# bn5_redraw.net
KiCad netlist of a schematic drawn in EAGLE
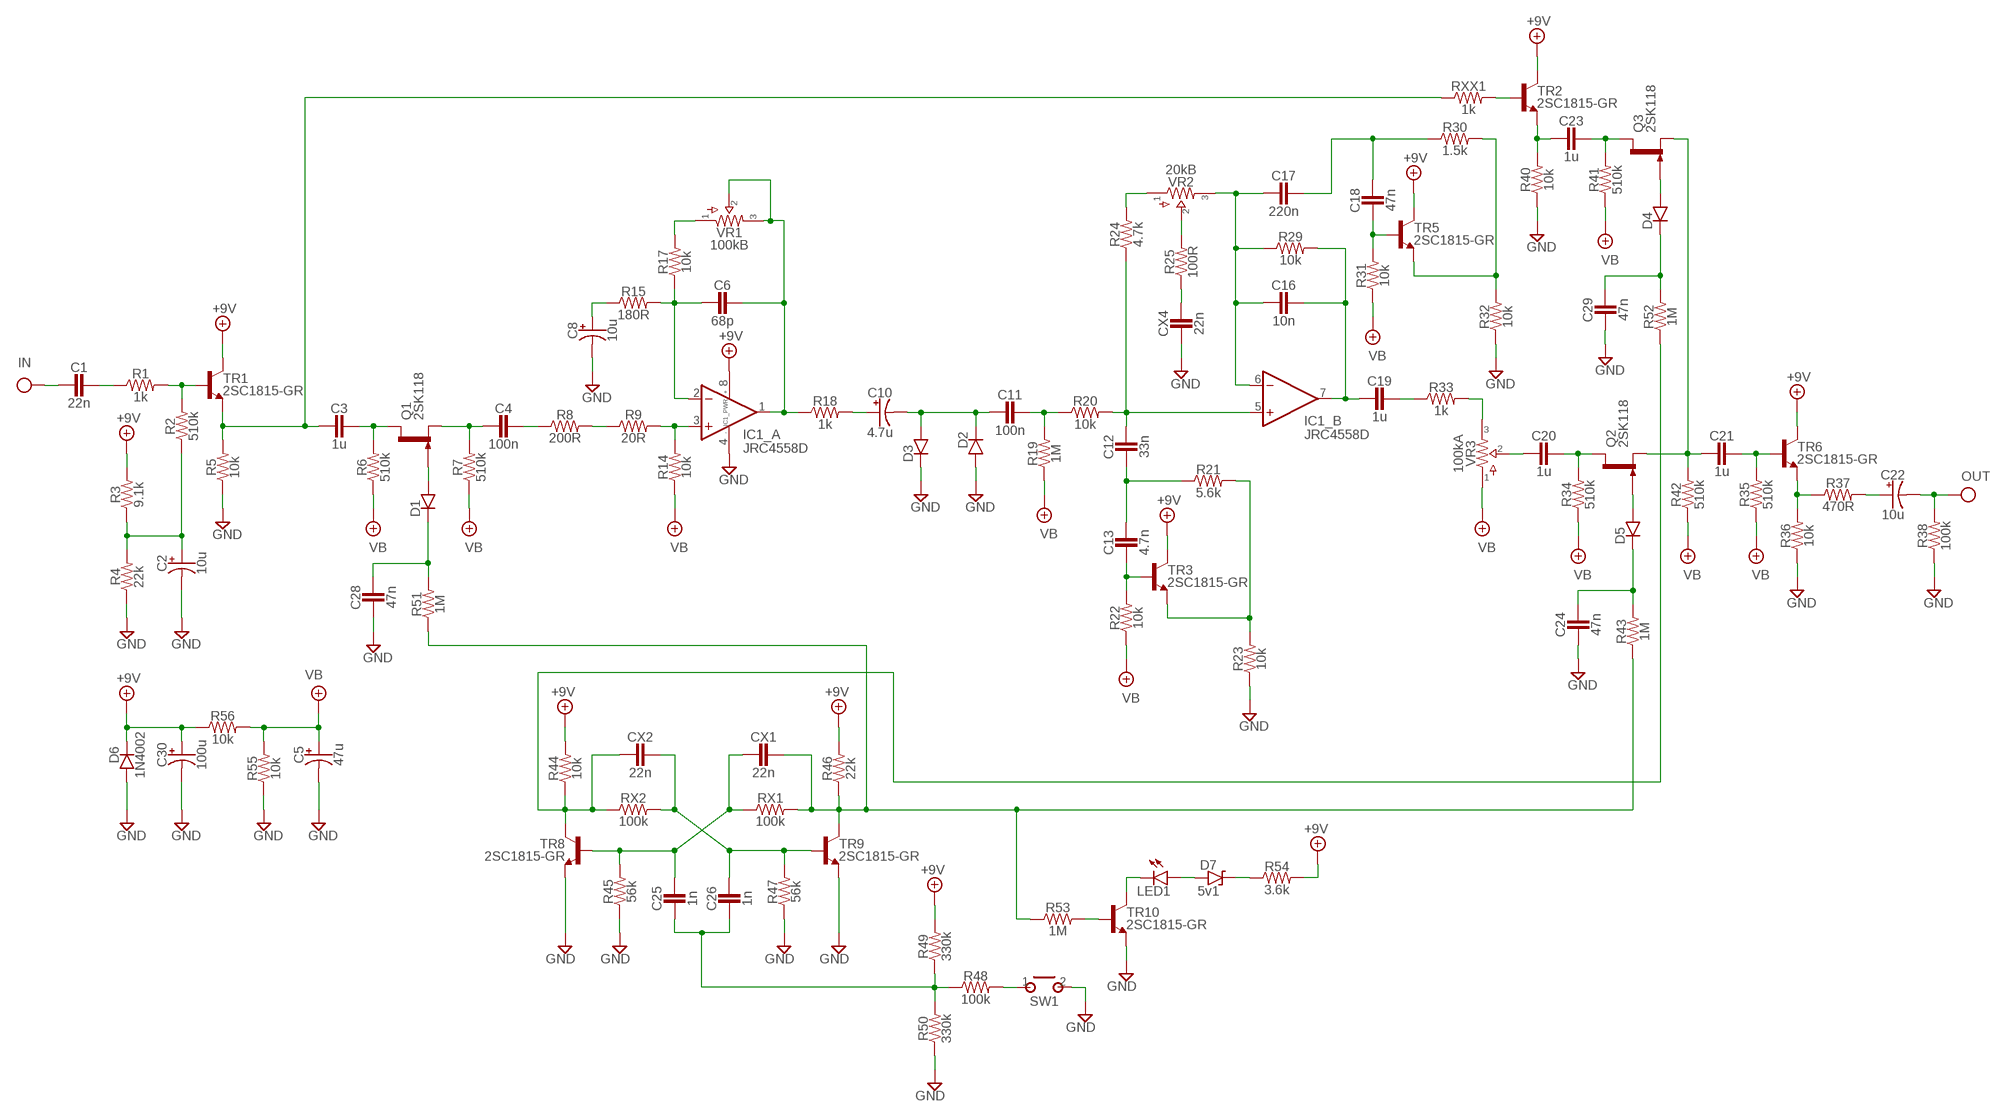
[diagram p0: schematic, sheet 1]

(export (version "E")
  (design (tool "Eeschema 10.0.6"))
  (components
    (comp (ref "C1")
      (value "22n")
      (footprint "eagle-import:BOX_SMALL")
      (libsource (lib "eagle-import") (part "CER/FILMBOX.1"))
    )
    (comp (ref "C2")
      (value "10u")
      (footprint "eagle-import:050_020")
      (libsource (lib "eagle-import") (part "0500"))
    )
    (comp (ref "C3")
      (value "1u")
      (footprint "eagle-import:BOX_SMALL")
      (libsource (lib "eagle-import") (part "CER/FILMBOX.1"))
    )
    (comp (ref "C4")
      (value "100n")
      (footprint "eagle-import:BOX_SMALL")
      (libsource (lib "eagle-import") (part "CER/FILMBOX.1"))
    )
    (comp (ref "C5")
      (value "47u")
      (footprint "eagle-import:050_020")
      (libsource (lib "eagle-import") (part "0500"))
    )
    (comp (ref "C6")
      (value "68p")
      (footprint "eagle-import:BOX_SMALL")
      (libsource (lib "eagle-import") (part "CER/FILMBOX.1"))
    )
    (comp (ref "C8")
      (value "10u")
      (footprint "eagle-import:050_020")
      (libsource (lib "eagle-import") (part "0500"))
    )
    (comp (ref "C10")
      (value "4.7u")
      (footprint "eagle-import:050_020")
      (libsource (lib "eagle-import") (part "0500"))
    )
    (comp (ref "C11")
      (value "100n")
      (footprint "eagle-import:BOX_SMALL")
      (libsource (lib "eagle-import") (part "CER/FILMBOX.1"))
    )
    (comp (ref "C12")
      (value "33n")
      (footprint "eagle-import:BOX_SMALL")
      (libsource (lib "eagle-import") (part "CER/FILMBOX.1"))
    )
    (comp (ref "C13")
      (value "4.7n")
      (footprint "eagle-import:BOX_SMALL")
      (libsource (lib "eagle-import") (part "CER/FILMBOX.1"))
    )
    (comp (ref "C16")
      (value "10n")
      (footprint "eagle-import:BOX_SMALL")
      (libsource (lib "eagle-import") (part "CER/FILMBOX.1"))
    )
    (comp (ref "C17")
      (value "220n")
      (footprint "eagle-import:BOX_SMALL")
      (libsource (lib "eagle-import") (part "CER/FILMBOX.1"))
    )
    (comp (ref "C18")
      (value "47n")
      (footprint "eagle-import:BOX_SMALL")
      (libsource (lib "eagle-import") (part "CER/FILMBOX.1"))
    )
    (comp (ref "C19")
      (value "1u")
      (footprint "eagle-import:BOX_SMALL")
      (libsource (lib "eagle-import") (part "CER/FILMBOX.1"))
    )
    (comp (ref "C20")
      (value "1u")
      (footprint "eagle-import:BOX_SMALL")
      (libsource (lib "eagle-import") (part "CER/FILMBOX.1"))
    )
    (comp (ref "C21")
      (value "1u")
      (footprint "eagle-import:BOX_SMALL")
      (libsource (lib "eagle-import") (part "CER/FILMBOX.1"))
    )
    (comp (ref "C22")
      (value "10u")
      (footprint "eagle-import:050_020")
      (libsource (lib "eagle-import") (part "0500"))
    )
    (comp (ref "C23")
      (value "1u")
      (footprint "eagle-import:BOX_SMALL")
      (libsource (lib "eagle-import") (part "CER/FILMBOX.1"))
    )
    (comp (ref "C24")
      (value "47n")
      (footprint "eagle-import:BOX_SMALL")
      (libsource (lib "eagle-import") (part "CER/FILMBOX.1"))
    )
    (comp (ref "C25")
      (value "1n")
      (footprint "eagle-import:BOX_SMALL")
      (libsource (lib "eagle-import") (part "CER/FILMBOX.1"))
    )
    (comp (ref "C26")
      (value "1n")
      (footprint "eagle-import:BOX_SMALL")
      (libsource (lib "eagle-import") (part "CER/FILMBOX.1"))
    )
    (comp (ref "C28")
      (value "47n")
      (footprint "eagle-import:BOX_SMALL")
      (libsource (lib "eagle-import") (part "CER/FILMBOX.1"))
    )
    (comp (ref "C29")
      (value "47n")
      (footprint "eagle-import:BOX_SMALL")
      (libsource (lib "eagle-import") (part "CER/FILMBOX.1"))
    )
    (comp (ref "C30")
      (value "100u")
      (footprint "eagle-import:050_020")
      (libsource (lib "eagle-import") (part "0500"))
    )
    (comp (ref "CX1")
      (value "22n")
      (footprint "eagle-import:BOX_SMALL")
      (libsource (lib "eagle-import") (part "CER/FILMBOX.1"))
    )
    (comp (ref "CX2")
      (value "22n")
      (footprint "eagle-import:BOX_SMALL")
      (libsource (lib "eagle-import") (part "CER/FILMBOX.1"))
    )
    (comp (ref "CX4")
      (value "22n")
      (footprint "eagle-import:BOX_SMALL")
      (libsource (lib "eagle-import") (part "CER/FILMBOX.1"))
    )
    (comp (ref "D1")
      (value "DO35.2")
      (footprint "eagle-import:DO35-2")
      (libsource (lib "eagle-import") (part "DO35.2"))
    )
    (comp (ref "D2")
      (value "DO35.2")
      (footprint "eagle-import:DO35-2")
      (libsource (lib "eagle-import") (part "DO35.2"))
    )
    (comp (ref "D3")
      (value "DO35.2")
      (footprint "eagle-import:DO35-2")
      (libsource (lib "eagle-import") (part "DO35.2"))
    )
    (comp (ref "D4")
      (value "DO35.2")
      (footprint "eagle-import:DO35-2")
      (libsource (lib "eagle-import") (part "DO35.2"))
    )
    (comp (ref "D5")
      (value "DO35.2")
      (footprint "eagle-import:DO35-2")
      (libsource (lib "eagle-import") (part "DO35.2"))
    )
    (comp (ref "D6")
      (value "1N4002")
      (footprint "eagle-import:DO35-2")
      (libsource (lib "eagle-import") (part "DO35.2"))
    )
    (comp (ref "D7")
      (value "5v1")
      (footprint "eagle-import:DO41-2")
      (libsource (lib "eagle-import") (part "ZENER.2"))
    )
    (comp (ref "IC1")
      (value "JRC4558D")
      (footprint "eagle-import:DIL0")
      (libsource (lib "eagle-import") (part "DUALTH"))
    )
    (comp (ref "LED1")
      (value "LED")
      (footprint "eagle-import:3MM_D")
      (libsource (lib "eagle-import") (part "LED"))
    )
    (comp (ref "Q1")
      (value "2SK118")
      (footprint "eagle-import:TO92-")
      (libsource (lib "eagle-import") (part "2N5457"))
    )
    (comp (ref "Q2")
      (value "2SK118")
      (footprint "eagle-import:TO92-")
      (libsource (lib "eagle-import") (part "2N5457"))
    )
    (comp (ref "Q3")
      (value "2SK118")
      (footprint "eagle-import:TO92-")
      (libsource (lib "eagle-import") (part "2N5457"))
    )
    (comp (ref "R1")
      (value "1k")
      (footprint "eagle-import:R0207_3")
      (libsource (lib "eagle-import") (part "R_.3B"))
    )
    (comp (ref "R2")
      (value "510k")
      (footprint "eagle-import:R0207_3")
      (libsource (lib "eagle-import") (part "R_.3B"))
    )
    (comp (ref "R3")
      (value "9.1k")
      (footprint "eagle-import:R0207_3")
      (libsource (lib "eagle-import") (part "R_.3B"))
    )
    (comp (ref "R4")
      (value "22k")
      (footprint "eagle-import:R0207_3")
      (libsource (lib "eagle-import") (part "R_.3B"))
    )
    (comp (ref "R5")
      (value "10k")
      (footprint "eagle-import:R0207_3")
      (libsource (lib "eagle-import") (part "R_.3B"))
    )
    (comp (ref "R6")
      (value "510k")
      (footprint "eagle-import:R0207_3")
      (libsource (lib "eagle-import") (part "R_.3B"))
    )
    (comp (ref "R7")
      (value "510k")
      (footprint "eagle-import:R0207_3")
      (libsource (lib "eagle-import") (part "R_.3B"))
    )
    (comp (ref "R8")
      (value "200R")
      (footprint "eagle-import:R0207_3")
      (libsource (lib "eagle-import") (part "R_.3B"))
    )
    (comp (ref "R9")
      (value "20R")
      (footprint "eagle-import:R0207_3")
      (libsource (lib "eagle-import") (part "R_.3B"))
    )
    (comp (ref "R14")
      (value "10k")
      (footprint "eagle-import:R0207_3")
      (libsource (lib "eagle-import") (part "R_.3B"))
    )
    (comp (ref "R15")
      (value "180R")
      (footprint "eagle-import:R0207_3")
      (libsource (lib "eagle-import") (part "R_.3B"))
    )
    (comp (ref "R17")
      (value "10k")
      (footprint "eagle-import:R0207_3")
      (libsource (lib "eagle-import") (part "R_.3B"))
    )
    (comp (ref "R18")
      (value "1k")
      (footprint "eagle-import:R0207_3")
      (libsource (lib "eagle-import") (part "R_.3B"))
    )
    (comp (ref "R19")
      (value "1M")
      (footprint "eagle-import:R0207_3")
      (libsource (lib "eagle-import") (part "R_.3B"))
    )
    (comp (ref "R20")
      (value "10k")
      (footprint "eagle-import:R0207_3")
      (libsource (lib "eagle-import") (part "R_.3B"))
    )
    (comp (ref "R21")
      (value "5.6k")
      (footprint "eagle-import:R0207_3")
      (libsource (lib "eagle-import") (part "R_.3B"))
    )
    (comp (ref "R22")
      (value "10k")
      (footprint "eagle-import:R0207_3")
      (libsource (lib "eagle-import") (part "R_.3B"))
    )
    (comp (ref "R23")
      (value "10k")
      (footprint "eagle-import:R0207_3")
      (libsource (lib "eagle-import") (part "R_.3B"))
    )
    (comp (ref "R24")
      (value "4.7k")
      (footprint "eagle-import:R0207_3")
      (libsource (lib "eagle-import") (part "R_.3B"))
    )
    (comp (ref "R25")
      (value "100R")
      (footprint "eagle-import:R0207_3")
      (libsource (lib "eagle-import") (part "R_.3B"))
    )
    (comp (ref "R29")
      (value "10k")
      (footprint "eagle-import:R0207_3")
      (libsource (lib "eagle-import") (part "R_.3B"))
    )
    (comp (ref "R30")
      (value "1.5k")
      (footprint "eagle-import:R0207_3")
      (libsource (lib "eagle-import") (part "R_.3B"))
    )
    (comp (ref "R31")
      (value "10k")
      (footprint "eagle-import:R0207_3")
      (libsource (lib "eagle-import") (part "R_.3B"))
    )
    (comp (ref "R32")
      (value "10k")
      (footprint "eagle-import:R0207_3")
      (libsource (lib "eagle-import") (part "R_.3B"))
    )
    (comp (ref "R33")
      (value "1k")
      (footprint "eagle-import:R0207_3")
      (libsource (lib "eagle-import") (part "R_.3B"))
    )
    (comp (ref "R34")
      (value "510k")
      (footprint "eagle-import:R0207_3")
      (libsource (lib "eagle-import") (part "R_.3B"))
    )
    (comp (ref "R35")
      (value "510k")
      (footprint "eagle-import:R0207_3")
      (libsource (lib "eagle-import") (part "R_.3B"))
    )
    (comp (ref "R36")
      (value "10k")
      (footprint "eagle-import:R0207_3")
      (libsource (lib "eagle-import") (part "R_.3B"))
    )
    (comp (ref "R37")
      (value "470R")
      (footprint "eagle-import:R0207_3")
      (libsource (lib "eagle-import") (part "R_.3B"))
    )
    (comp (ref "R38")
      (value "100k")
      (footprint "eagle-import:R0207_3")
      (libsource (lib "eagle-import") (part "R_.3B"))
    )
    (comp (ref "R40")
      (value "10k")
      (footprint "eagle-import:R0207_3")
      (libsource (lib "eagle-import") (part "R_.3B"))
    )
    (comp (ref "R41")
      (value "510k")
      (footprint "eagle-import:R0207_3")
      (libsource (lib "eagle-import") (part "R_.3B"))
    )
    (comp (ref "R42")
      (value "510k")
      (footprint "eagle-import:R0207_3")
      (libsource (lib "eagle-import") (part "R_.3B"))
    )
    (comp (ref "R43")
      (value "1M")
      (footprint "eagle-import:R0207_3")
      (libsource (lib "eagle-import") (part "R_.3B"))
    )
    (comp (ref "R44")
      (value "10k")
      (footprint "eagle-import:R0207_3")
      (libsource (lib "eagle-import") (part "R_.3B"))
    )
    (comp (ref "R45")
      (value "56k")
      (footprint "eagle-import:R0207_3")
      (libsource (lib "eagle-import") (part "R_.3B"))
    )
    (comp (ref "R46")
      (value "22k")
      (footprint "eagle-import:R0207_3")
      (libsource (lib "eagle-import") (part "R_.3B"))
    )
    (comp (ref "R47")
      (value "56k")
      (footprint "eagle-import:R0207_3")
      (libsource (lib "eagle-import") (part "R_.3B"))
    )
    (comp (ref "R48")
      (value "100k")
      (footprint "eagle-import:R0207_3")
      (libsource (lib "eagle-import") (part "R_.3B"))
    )
    (comp (ref "R49")
      (value "330k")
      (footprint "eagle-import:R0207_3")
      (libsource (lib "eagle-import") (part "R_.3B"))
    )
    (comp (ref "R50")
      (value "330k")
      (footprint "eagle-import:R0207_3")
      (libsource (lib "eagle-import") (part "R_.3B"))
    )
    (comp (ref "R51")
      (value "1M")
      (footprint "eagle-import:R0207_3")
      (libsource (lib "eagle-import") (part "R_.3B"))
    )
    (comp (ref "R52")
      (value "1M")
      (footprint "eagle-import:R0207_3")
      (libsource (lib "eagle-import") (part "R_.3B"))
    )
    (comp (ref "R53")
      (value "1M")
      (footprint "eagle-import:R0207_3")
      (libsource (lib "eagle-import") (part "R_.3B"))
    )
    (comp (ref "R54")
      (value "3.6k")
      (footprint "eagle-import:R0207_3")
      (libsource (lib "eagle-import") (part "R_.3B"))
    )
    (comp (ref "R55")
      (value "10k")
      (footprint "eagle-import:R0207_3")
      (libsource (lib "eagle-import") (part "R_.3B"))
    )
    (comp (ref "R56")
      (value "10k")
      (footprint "eagle-import:R0207_3")
      (libsource (lib "eagle-import") (part "R_.3B"))
    )
    (comp (ref "RX1")
      (value "100k")
      (footprint "eagle-import:R0207_3")
      (libsource (lib "eagle-import") (part "R_.3B"))
    )
    (comp (ref "RX2")
      (value "100k")
      (footprint "eagle-import:R0207_3")
      (libsource (lib "eagle-import") (part "R_.3B"))
    )
    (comp (ref "RXX1")
      (value "1k")
      (footprint "eagle-import:R0207_3")
      (libsource (lib "eagle-import") (part "R_.3B"))
    )
    (comp (ref "SW1")
      (value "MOMENTARY")
      (footprint "eagle-import:SPST")
      (libsource (lib "eagle-import") (part "MOMENTARY"))
    )
    (comp (ref "TR1")
      (value "2SC1815-GR")
      (footprint "eagle-import:TO92-")
      (libsource (lib "eagle-import") (part "2SC828A"))
    )
    (comp (ref "TR2")
      (value "2SC1815-GR")
      (footprint "eagle-import:TO92-")
      (libsource (lib "eagle-import") (part "2SC828A"))
    )
    (comp (ref "TR3")
      (value "2SC1815-GR")
      (footprint "eagle-import:TO92-")
      (libsource (lib "eagle-import") (part "2SC828A"))
    )
    (comp (ref "TR5")
      (value "2SC1815-GR")
      (footprint "eagle-import:TO92-")
      (libsource (lib "eagle-import") (part "2SC828A"))
    )
    (comp (ref "TR6")
      (value "2SC1815-GR")
      (footprint "eagle-import:TO92-")
      (libsource (lib "eagle-import") (part "2SC828A"))
    )
    (comp (ref "TR8")
      (value "2SC1815-GR")
      (footprint "eagle-import:TO92-")
      (libsource (lib "eagle-import") (part "2SC828A"))
    )
    (comp (ref "TR9")
      (value "2SC1815-GR")
      (footprint "eagle-import:TO92-")
      (libsource (lib "eagle-import") (part "2SC828A"))
    )
    (comp (ref "TR10")
      (value "2SC1815-GR")
      (footprint "eagle-import:TO92-")
      (libsource (lib "eagle-import") (part "2SC828A"))
    )
    (comp (ref "VR1")
      (value "100kB")
      (footprint "eagle-import:16MM")
      (libsource (lib "eagle-import") (part "POTS16MM"))
    )
    (comp (ref "VR2")
      (value "20kB")
      (footprint "eagle-import:16MM")
      (libsource (lib "eagle-import") (part "POTS16MM"))
    )
    (comp (ref "VR3")
      (value "100kA")
      (footprint "eagle-import:16MM")
      (libsource (lib "eagle-import") (part "POTS16MM"))
    )
  )
  (nets
    (net (code "1") (name "+9V") (class "Default")
      (node (ref "C30") (pin "+") (pinfunction "+_+") (pintype "passive"))
      (node (ref "D6") (pin "C") (pinfunction "C_C") (pintype "passive"))
      (node (ref "IC1") (pin "8") (pinfunction "V+_8") (pintype "power_in"))
      (node (ref "R3") (pin "2") (pinfunction "2_2") (pintype "passive"))
      (node (ref "R44") (pin "2") (pinfunction "2_2") (pintype "passive"))
      (node (ref "R46") (pin "2") (pinfunction "2_2") (pintype "passive"))
      (node (ref "R49") (pin "2") (pinfunction "2_2") (pintype "passive"))
      (node (ref "R54") (pin "2") (pinfunction "2_2") (pintype "passive"))
      (node (ref "R56") (pin "1") (pinfunction "1_1") (pintype "passive"))
      (node (ref "TR1") (pin "2") (pinfunction "C_2") (pintype "passive"))
      (node (ref "TR2") (pin "2") (pinfunction "C_2") (pintype "passive"))
      (node (ref "TR3") (pin "2") (pinfunction "C_2") (pintype "passive"))
      (node (ref "TR5") (pin "2") (pinfunction "C_2") (pintype "passive"))
      (node (ref "TR6") (pin "2") (pinfunction "C_2") (pintype "passive"))
    )
    (net (code "2") (name "GND") (class "Default")
      (node (ref "C2") (pin "-") (pinfunction "-_-") (pintype "passive"))
      (node (ref "C24") (pin "2") (pinfunction "2_2") (pintype "passive"))
      (node (ref "C28") (pin "2") (pinfunction "2_2") (pintype "passive"))
      (node (ref "C29") (pin "2") (pinfunction "2_2") (pintype "passive"))
      (node (ref "C30") (pin "-") (pinfunction "-_-") (pintype "passive"))
      (node (ref "C5") (pin "-") (pinfunction "-_-") (pintype "passive"))
      (node (ref "C8") (pin "-") (pinfunction "-_-") (pintype "passive"))
      (node (ref "CX4") (pin "2") (pinfunction "2_2") (pintype "passive"))
      (node (ref "D2") (pin "A") (pinfunction "A_A") (pintype "passive"))
      (node (ref "D3") (pin "C") (pinfunction "C_C") (pintype "passive"))
      (node (ref "D6") (pin "A") (pinfunction "A_A") (pintype "passive"))
      (node (ref "IC1") (pin "4") (pinfunction "V-_4") (pintype "power_in"))
      (node (ref "R23") (pin "1") (pinfunction "1_1") (pintype "passive"))
      (node (ref "R32") (pin "1") (pinfunction "1_1") (pintype "passive"))
      (node (ref "R36") (pin "1") (pinfunction "1_1") (pintype "passive"))
      (node (ref "R38") (pin "1") (pinfunction "1_1") (pintype "passive"))
      (node (ref "R4") (pin "1") (pinfunction "1_1") (pintype "passive"))
      (node (ref "R40") (pin "1") (pinfunction "1_1") (pintype "passive"))
      (node (ref "R45") (pin "1") (pinfunction "1_1") (pintype "passive"))
      (node (ref "R47") (pin "1") (pinfunction "1_1") (pintype "passive"))
      (node (ref "R5") (pin "1") (pinfunction "1_1") (pintype "passive"))
      (node (ref "R50") (pin "1") (pinfunction "1_1") (pintype "passive"))
      (node (ref "R55") (pin "1") (pinfunction "1_1") (pintype "passive"))
      (node (ref "SW1") (pin "2") (pinfunction "S_2") (pintype "passive"))
      (node (ref "TR10") (pin "3") (pinfunction "E_3") (pintype "passive"))
      (node (ref "TR8") (pin "3") (pinfunction "E_3") (pintype "passive"))
      (node (ref "TR9") (pin "3") (pinfunction "E_3") (pintype "passive"))
    )
    (net (code "3") (name "IN") (class "Default")
      (node (ref "C1") (pin "2") (pinfunction "2_2") (pintype "passive"))
    )
    (net (code "4") (name "Net-(C1-Pad1)") (class "Default")
      (node (ref "C1") (pin "1") (pinfunction "1_1") (pintype "passive"))
      (node (ref "R1") (pin "1") (pinfunction "1_1") (pintype "passive"))
    )
    (net (code "5") (name "Net-(C2-Pad+)") (class "Default")
      (node (ref "C2") (pin "+") (pinfunction "+_+") (pintype "passive"))
      (node (ref "R2") (pin "1") (pinfunction "1_1") (pintype "passive"))
      (node (ref "R3") (pin "1") (pinfunction "1_1") (pintype "passive"))
      (node (ref "R4") (pin "2") (pinfunction "2_2") (pintype "passive"))
    )
    (net (code "6") (name "Net-(C4-Pad1)") (class "Default")
      (node (ref "C4") (pin "1") (pinfunction "1_1") (pintype "passive"))
      (node (ref "R8") (pin "1") (pinfunction "1_1") (pintype "passive"))
    )
    (net (code "7") (name "Net-(C8-Pad+)") (class "Default")
      (node (ref "C8") (pin "+") (pinfunction "+_+") (pintype "passive"))
      (node (ref "R15") (pin "1") (pinfunction "1_1") (pintype "passive"))
    )
    (net (code "8") (name "Net-(C10-Pad+)") (class "Default")
      (node (ref "C10") (pin "+") (pinfunction "+_+") (pintype "passive"))
      (node (ref "R18") (pin "2") (pinfunction "2_2") (pintype "passive"))
    )
    (net (code "9") (name "Net-(C10-Pad-)") (class "Default")
      (node (ref "C10") (pin "-") (pinfunction "-_-") (pintype "passive"))
      (node (ref "C11") (pin "2") (pinfunction "2_2") (pintype "passive"))
      (node (ref "D2") (pin "C") (pinfunction "C_C") (pintype "passive"))
      (node (ref "D3") (pin "A") (pinfunction "A_A") (pintype "passive"))
    )
    (net (code "10") (name "Net-(C11-Pad1)") (class "Default")
      (node (ref "C11") (pin "1") (pinfunction "1_1") (pintype "passive"))
      (node (ref "R19") (pin "2") (pinfunction "2_2") (pintype "passive"))
      (node (ref "R20") (pin "1") (pinfunction "1_1") (pintype "passive"))
    )
    (net (code "11") (name "Net-(C12-Pad2)") (class "Default")
      (node (ref "C12") (pin "2") (pinfunction "2_2") (pintype "passive"))
      (node (ref "C13") (pin "1") (pinfunction "1_1") (pintype "passive"))
      (node (ref "R21") (pin "1") (pinfunction "1_1") (pintype "passive"))
    )
    (net (code "12") (name "Net-(C17-Pad1)") (class "Default")
      (node (ref "C17") (pin "1") (pinfunction "1_1") (pintype "passive"))
      (node (ref "C18") (pin "1") (pinfunction "1_1") (pintype "passive"))
      (node (ref "R30") (pin "1") (pinfunction "1_1") (pintype "passive"))
    )
    (net (code "13") (name "Net-(C19-Pad1)") (class "Default")
      (node (ref "C19") (pin "1") (pinfunction "1_1") (pintype "passive"))
      (node (ref "R33") (pin "1") (pinfunction "1_1") (pintype "passive"))
    )
    (net (code "14") (name "Net-(C20-Pad2)") (class "Default")
      (node (ref "C20") (pin "2") (pinfunction "2_2") (pintype "passive"))
      (node (ref "VR3") (pin "2") (pinfunction "2_2") (pintype "passive"))
    )
    (net (code "15") (name "Net-(C22-Pad+)") (class "Default")
      (node (ref "C22") (pin "+") (pinfunction "+_+") (pintype "passive"))
      (node (ref "R37") (pin "2") (pinfunction "2_2") (pintype "passive"))
    )
    (net (code "16") (name "Net-(C24-Pad1)") (class "Default")
      (node (ref "C24") (pin "1") (pinfunction "1_1") (pintype "passive"))
      (node (ref "D5") (pin "C") (pinfunction "C_C") (pintype "passive"))
      (node (ref "R43") (pin "2") (pinfunction "2_2") (pintype "passive"))
    )
    (net (code "17") (name "Net-(C25-Pad2)") (class "Default")
      (node (ref "C25") (pin "2") (pinfunction "2_2") (pintype "passive"))
      (node (ref "C26") (pin "2") (pinfunction "2_2") (pintype "passive"))
      (node (ref "R48") (pin "1") (pinfunction "1_1") (pintype "passive"))
      (node (ref "R49") (pin "1") (pinfunction "1_1") (pintype "passive"))
      (node (ref "R50") (pin "2") (pinfunction "2_2") (pintype "passive"))
    )
    (net (code "18") (name "Net-(C28-Pad1)") (class "Default")
      (node (ref "C28") (pin "1") (pinfunction "1_1") (pintype "passive"))
      (node (ref "D1") (pin "C") (pinfunction "C_C") (pintype "passive"))
      (node (ref "R51") (pin "2") (pinfunction "2_2") (pintype "passive"))
    )
    (net (code "19") (name "Net-(C29-Pad1)") (class "Default")
      (node (ref "C29") (pin "1") (pinfunction "1_1") (pintype "passive"))
      (node (ref "D4") (pin "C") (pinfunction "C_C") (pintype "passive"))
      (node (ref "R52") (pin "2") (pinfunction "2_2") (pintype "passive"))
    )
    (net (code "20") (name "Net-(CX4-Pad1)") (class "Default")
      (node (ref "CX4") (pin "1") (pinfunction "1_1") (pintype "passive"))
      (node (ref "R25") (pin "1") (pinfunction "1_1") (pintype "passive"))
    )
    (net (code "21") (name "Net-(D7-PadC)") (class "Default")
      (node (ref "D7") (pin "C") (pinfunction "C_C") (pintype "passive"))
      (node (ref "R54") (pin "1") (pinfunction "1_1") (pintype "passive"))
    )
    (net (code "22") (name "Net-(IC1A-+IN)") (class "Default")
      (node (ref "IC1") (pin "3") (pinfunction "+IN_3") (pintype "input"))
      (node (ref "R14") (pin "2") (pinfunction "2_2") (pintype "passive"))
      (node (ref "R9") (pin "2") (pinfunction "2_2") (pintype "passive"))
    )
    (net (code "23") (name "Net-(IC1A--IN)") (class "Default")
      (node (ref "C6") (pin "2") (pinfunction "2_2") (pintype "passive"))
      (node (ref "IC1") (pin "2") (pinfunction "-IN_2") (pintype "input"))
      (node (ref "R15") (pin "2") (pinfunction "2_2") (pintype "passive"))
      (node (ref "R17") (pin "1") (pinfunction "1_1") (pintype "passive"))
    )
    (net (code "24") (name "Net-(IC1A-OUT)") (class "Default")
      (node (ref "C6") (pin "1") (pinfunction "1_1") (pintype "passive"))
      (node (ref "IC1") (pin "1") (pinfunction "OUT_1") (pintype "output"))
      (node (ref "R18") (pin "1") (pinfunction "1_1") (pintype "passive"))
      (node (ref "VR1") (pin "2") (pinfunction "2_2") (pintype "passive"))
      (node (ref "VR1") (pin "3") (pinfunction "3_3") (pintype "passive"))
    )
    (net (code "25") (name "Net-(IC1B-+IN)") (class "Default")
      (node (ref "C12") (pin "1") (pinfunction "1_1") (pintype "passive"))
      (node (ref "IC1") (pin "5") (pinfunction "+IN_5") (pintype "input"))
      (node (ref "R20") (pin "2") (pinfunction "2_2") (pintype "passive"))
      (node (ref "R24") (pin "1") (pinfunction "1_1") (pintype "passive"))
    )
    (net (code "26") (name "Net-(IC1B--IN)") (class "Default")
      (node (ref "C16") (pin "2") (pinfunction "2_2") (pintype "passive"))
      (node (ref "C17") (pin "2") (pinfunction "2_2") (pintype "passive"))
      (node (ref "IC1") (pin "6") (pinfunction "-IN_6") (pintype "input"))
      (node (ref "R29") (pin "1") (pinfunction "1_1") (pintype "passive"))
      (node (ref "VR2") (pin "3") (pinfunction "3_3") (pintype "passive"))
    )
    (net (code "27") (name "Net-(IC1B-OUT)") (class "Default")
      (node (ref "C16") (pin "1") (pinfunction "1_1") (pintype "passive"))
      (node (ref "C19") (pin "2") (pinfunction "2_2") (pintype "passive"))
      (node (ref "IC1") (pin "7") (pinfunction "OUT_7") (pintype "output"))
      (node (ref "R29") (pin "2") (pinfunction "2_2") (pintype "passive"))
    )
    (net (code "28") (name "Net-(LED1-A)") (class "Default")
      (node (ref "D7") (pin "A") (pinfunction "A_A") (pintype "passive"))
      (node (ref "LED1") (pin "ANODE") (pinfunction "A_ANODE") (pintype "passive"))
    )
    (net (code "29") (name "Net-(LED1-C)") (class "Default")
      (node (ref "LED1") (pin "P$1") (pinfunction "C_P$1") (pintype "passive"))
      (node (ref "TR10") (pin "2") (pinfunction "C_2") (pintype "passive"))
    )
    (net (code "30") (name "Net-(Q1-D)") (class "Default")
      (node (ref "C3") (pin "1") (pinfunction "1_1") (pintype "passive"))
      (node (ref "Q1") (pin "3") (pinfunction "D_3") (pintype "passive"))
      (node (ref "R6") (pin "2") (pinfunction "2_2") (pintype "passive"))
    )
    (net (code "31") (name "Net-(Q1-G)") (class "Default")
      (node (ref "D1") (pin "A") (pinfunction "A_A") (pintype "passive"))
      (node (ref "Q1") (pin "1") (pinfunction "G_1") (pintype "passive"))
    )
    (net (code "32") (name "Net-(Q1-S)") (class "Default")
      (node (ref "C4") (pin "2") (pinfunction "2_2") (pintype "passive"))
      (node (ref "Q1") (pin "2") (pinfunction "S_2") (pintype "passive"))
      (node (ref "R7") (pin "2") (pinfunction "2_2") (pintype "passive"))
    )
    (net (code "33") (name "Net-(Q2-D)") (class "Default")
      (node (ref "C20") (pin "1") (pinfunction "1_1") (pintype "passive"))
      (node (ref "Q2") (pin "3") (pinfunction "D_3") (pintype "passive"))
      (node (ref "R34") (pin "2") (pinfunction "2_2") (pintype "passive"))
    )
    (net (code "34") (name "Net-(Q2-G)") (class "Default")
      (node (ref "D5") (pin "A") (pinfunction "A_A") (pintype "passive"))
      (node (ref "Q2") (pin "1") (pinfunction "G_1") (pintype "passive"))
    )
    (net (code "35") (name "Net-(Q2-S)") (class "Default")
      (node (ref "C21") (pin "2") (pinfunction "2_2") (pintype "passive"))
      (node (ref "Q2") (pin "2") (pinfunction "S_2") (pintype "passive"))
      (node (ref "Q3") (pin "2") (pinfunction "S_2") (pintype "passive"))
      (node (ref "R42") (pin "2") (pinfunction "2_2") (pintype "passive"))
    )
    (net (code "36") (name "Net-(Q3-D)") (class "Default")
      (node (ref "C23") (pin "1") (pinfunction "1_1") (pintype "passive"))
      (node (ref "Q3") (pin "3") (pinfunction "D_3") (pintype "passive"))
      (node (ref "R41") (pin "2") (pinfunction "2_2") (pintype "passive"))
    )
    (net (code "37") (name "Net-(Q3-G)") (class "Default")
      (node (ref "D4") (pin "A") (pinfunction "A_A") (pintype "passive"))
      (node (ref "Q3") (pin "1") (pinfunction "G_1") (pintype "passive"))
    )
    (net (code "38") (name "Net-(R8-Pad2)") (class "Default")
      (node (ref "R8") (pin "2") (pinfunction "2_2") (pintype "passive"))
      (node (ref "R9") (pin "1") (pinfunction "1_1") (pintype "passive"))
    )
    (net (code "39") (name "Net-(R17-Pad2)") (class "Default")
      (node (ref "R17") (pin "2") (pinfunction "2_2") (pintype "passive"))
      (node (ref "VR1") (pin "1") (pinfunction "1_1") (pintype "passive"))
    )
    (net (code "40") (name "Net-(R24-Pad2)") (class "Default")
      (node (ref "R24") (pin "2") (pinfunction "2_2") (pintype "passive"))
      (node (ref "VR2") (pin "1") (pinfunction "1_1") (pintype "passive"))
    )
    (net (code "41") (name "Net-(R25-Pad2)") (class "Default")
      (node (ref "R25") (pin "2") (pinfunction "2_2") (pintype "passive"))
      (node (ref "VR2") (pin "2") (pinfunction "2_2") (pintype "passive"))
    )
    (net (code "42") (name "Net-(R33-Pad2)") (class "Default")
      (node (ref "R33") (pin "2") (pinfunction "2_2") (pintype "passive"))
      (node (ref "VR3") (pin "3") (pinfunction "3_3") (pintype "passive"))
    )
    (net (code "43") (name "Net-(SW1-P)") (class "Default")
      (node (ref "R48") (pin "2") (pinfunction "2_2") (pintype "passive"))
      (node (ref "SW1") (pin "1") (pinfunction "P_1") (pintype "passive"))
    )
    (net (code "44") (name "Net-(TR1-B)") (class "Default")
      (node (ref "R1") (pin "2") (pinfunction "2_2") (pintype "passive"))
      (node (ref "R2") (pin "2") (pinfunction "2_2") (pintype "passive"))
      (node (ref "TR1") (pin "1") (pinfunction "B_1") (pintype "passive"))
    )
    (net (code "45") (name "Net-(TR1-E)") (class "Default")
      (node (ref "C3") (pin "2") (pinfunction "2_2") (pintype "passive"))
      (node (ref "R5") (pin "2") (pinfunction "2_2") (pintype "passive"))
      (node (ref "RXX1") (pin "1") (pinfunction "1_1") (pintype "passive"))
      (node (ref "TR1") (pin "3") (pinfunction "E_3") (pintype "passive"))
    )
    (net (code "46") (name "Net-(TR2-B)") (class "Default")
      (node (ref "RXX1") (pin "2") (pinfunction "2_2") (pintype "passive"))
      (node (ref "TR2") (pin "1") (pinfunction "B_1") (pintype "passive"))
    )
    (net (code "47") (name "Net-(TR2-E)") (class "Default")
      (node (ref "C23") (pin "2") (pinfunction "2_2") (pintype "passive"))
      (node (ref "R40") (pin "2") (pinfunction "2_2") (pintype "passive"))
      (node (ref "TR2") (pin "3") (pinfunction "E_3") (pintype "passive"))
    )
    (net (code "48") (name "Net-(TR3-B)") (class "Default")
      (node (ref "C13") (pin "2") (pinfunction "2_2") (pintype "passive"))
      (node (ref "R22") (pin "2") (pinfunction "2_2") (pintype "passive"))
      (node (ref "TR3") (pin "1") (pinfunction "B_1") (pintype "passive"))
    )
    (net (code "49") (name "Net-(TR3-E)") (class "Default")
      (node (ref "R21") (pin "2") (pinfunction "2_2") (pintype "passive"))
      (node (ref "R23") (pin "2") (pinfunction "2_2") (pintype "passive"))
      (node (ref "TR3") (pin "3") (pinfunction "E_3") (pintype "passive"))
    )
    (net (code "50") (name "Net-(TR5-B)") (class "Default")
      (node (ref "C18") (pin "2") (pinfunction "2_2") (pintype "passive"))
      (node (ref "R31") (pin "2") (pinfunction "2_2") (pintype "passive"))
      (node (ref "TR5") (pin "1") (pinfunction "B_1") (pintype "passive"))
    )
    (net (code "51") (name "Net-(TR5-E)") (class "Default")
      (node (ref "R30") (pin "2") (pinfunction "2_2") (pintype "passive"))
      (node (ref "R32") (pin "2") (pinfunction "2_2") (pintype "passive"))
      (node (ref "TR5") (pin "3") (pinfunction "E_3") (pintype "passive"))
    )
    (net (code "52") (name "Net-(TR6-B)") (class "Default")
      (node (ref "C21") (pin "1") (pinfunction "1_1") (pintype "passive"))
      (node (ref "R35") (pin "2") (pinfunction "2_2") (pintype "passive"))
      (node (ref "TR6") (pin "1") (pinfunction "B_1") (pintype "passive"))
    )
    (net (code "53") (name "Net-(TR6-E)") (class "Default")
      (node (ref "R36") (pin "2") (pinfunction "2_2") (pintype "passive"))
      (node (ref "R37") (pin "1") (pinfunction "1_1") (pintype "passive"))
      (node (ref "TR6") (pin "3") (pinfunction "E_3") (pintype "passive"))
    )
    (net (code "54") (name "Net-(TR8-B)") (class "Default")
      (node (ref "C25") (pin "1") (pinfunction "1_1") (pintype "passive"))
      (node (ref "CX1") (pin "2") (pinfunction "2_2") (pintype "passive"))
      (node (ref "R45") (pin "2") (pinfunction "2_2") (pintype "passive"))
      (node (ref "RX1") (pin "1") (pinfunction "1_1") (pintype "passive"))
      (node (ref "TR8") (pin "1") (pinfunction "B_1") (pintype "passive"))
    )
    (net (code "55") (name "Net-(TR8-C)") (class "Default")
      (node (ref "CX2") (pin "2") (pinfunction "2_2") (pintype "passive"))
      (node (ref "R44") (pin "1") (pinfunction "1_1") (pintype "passive"))
      (node (ref "R52") (pin "1") (pinfunction "1_1") (pintype "passive"))
      (node (ref "RX2") (pin "1") (pinfunction "1_1") (pintype "passive"))
      (node (ref "TR8") (pin "2") (pinfunction "C_2") (pintype "passive"))
    )
    (net (code "56") (name "Net-(TR9-B)") (class "Default")
      (node (ref "C26") (pin "1") (pinfunction "1_1") (pintype "passive"))
      (node (ref "CX2") (pin "1") (pinfunction "1_1") (pintype "passive"))
      (node (ref "R47") (pin "2") (pinfunction "2_2") (pintype "passive"))
      (node (ref "RX2") (pin "2") (pinfunction "2_2") (pintype "passive"))
      (node (ref "TR9") (pin "1") (pinfunction "B_1") (pintype "passive"))
    )
    (net (code "57") (name "Net-(TR9-C)") (class "Default")
      (node (ref "CX1") (pin "1") (pinfunction "1_1") (pintype "passive"))
      (node (ref "R43") (pin "1") (pinfunction "1_1") (pintype "passive"))
      (node (ref "R46") (pin "1") (pinfunction "1_1") (pintype "passive"))
      (node (ref "R51") (pin "1") (pinfunction "1_1") (pintype "passive"))
      (node (ref "R53") (pin "1") (pinfunction "1_1") (pintype "passive"))
      (node (ref "RX1") (pin "2") (pinfunction "2_2") (pintype "passive"))
      (node (ref "TR9") (pin "2") (pinfunction "C_2") (pintype "passive"))
    )
    (net (code "58") (name "Net-(TR10-B)") (class "Default")
      (node (ref "R53") (pin "2") (pinfunction "2_2") (pintype "passive"))
      (node (ref "TR10") (pin "1") (pinfunction "B_1") (pintype "passive"))
    )
    (net (code "59") (name "OUT") (class "Default")
      (node (ref "C22") (pin "-") (pinfunction "-_-") (pintype "passive"))
      (node (ref "R38") (pin "2") (pinfunction "2_2") (pintype "passive"))
    )
    (net (code "60") (name "VB") (class "Default")
      (node (ref "C5") (pin "+") (pinfunction "+_+") (pintype "passive"))
      (node (ref "R14") (pin "1") (pinfunction "1_1") (pintype "passive"))
      (node (ref "R19") (pin "1") (pinfunction "1_1") (pintype "passive"))
      (node (ref "R22") (pin "1") (pinfunction "1_1") (pintype "passive"))
      (node (ref "R31") (pin "1") (pinfunction "1_1") (pintype "passive"))
      (node (ref "R34") (pin "1") (pinfunction "1_1") (pintype "passive"))
      (node (ref "R35") (pin "1") (pinfunction "1_1") (pintype "passive"))
      (node (ref "R41") (pin "1") (pinfunction "1_1") (pintype "passive"))
      (node (ref "R42") (pin "1") (pinfunction "1_1") (pintype "passive"))
      (node (ref "R55") (pin "2") (pinfunction "2_2") (pintype "passive"))
      (node (ref "R56") (pin "2") (pinfunction "2_2") (pintype "passive"))
      (node (ref "R6") (pin "1") (pinfunction "1_1") (pintype "passive"))
      (node (ref "R7") (pin "1") (pinfunction "1_1") (pintype "passive"))
      (node (ref "VR3") (pin "1") (pinfunction "1_1") (pintype "passive"))
    )
  )
)
